# main.net
KiCad netlist of a schematic drawn in Altium Designer
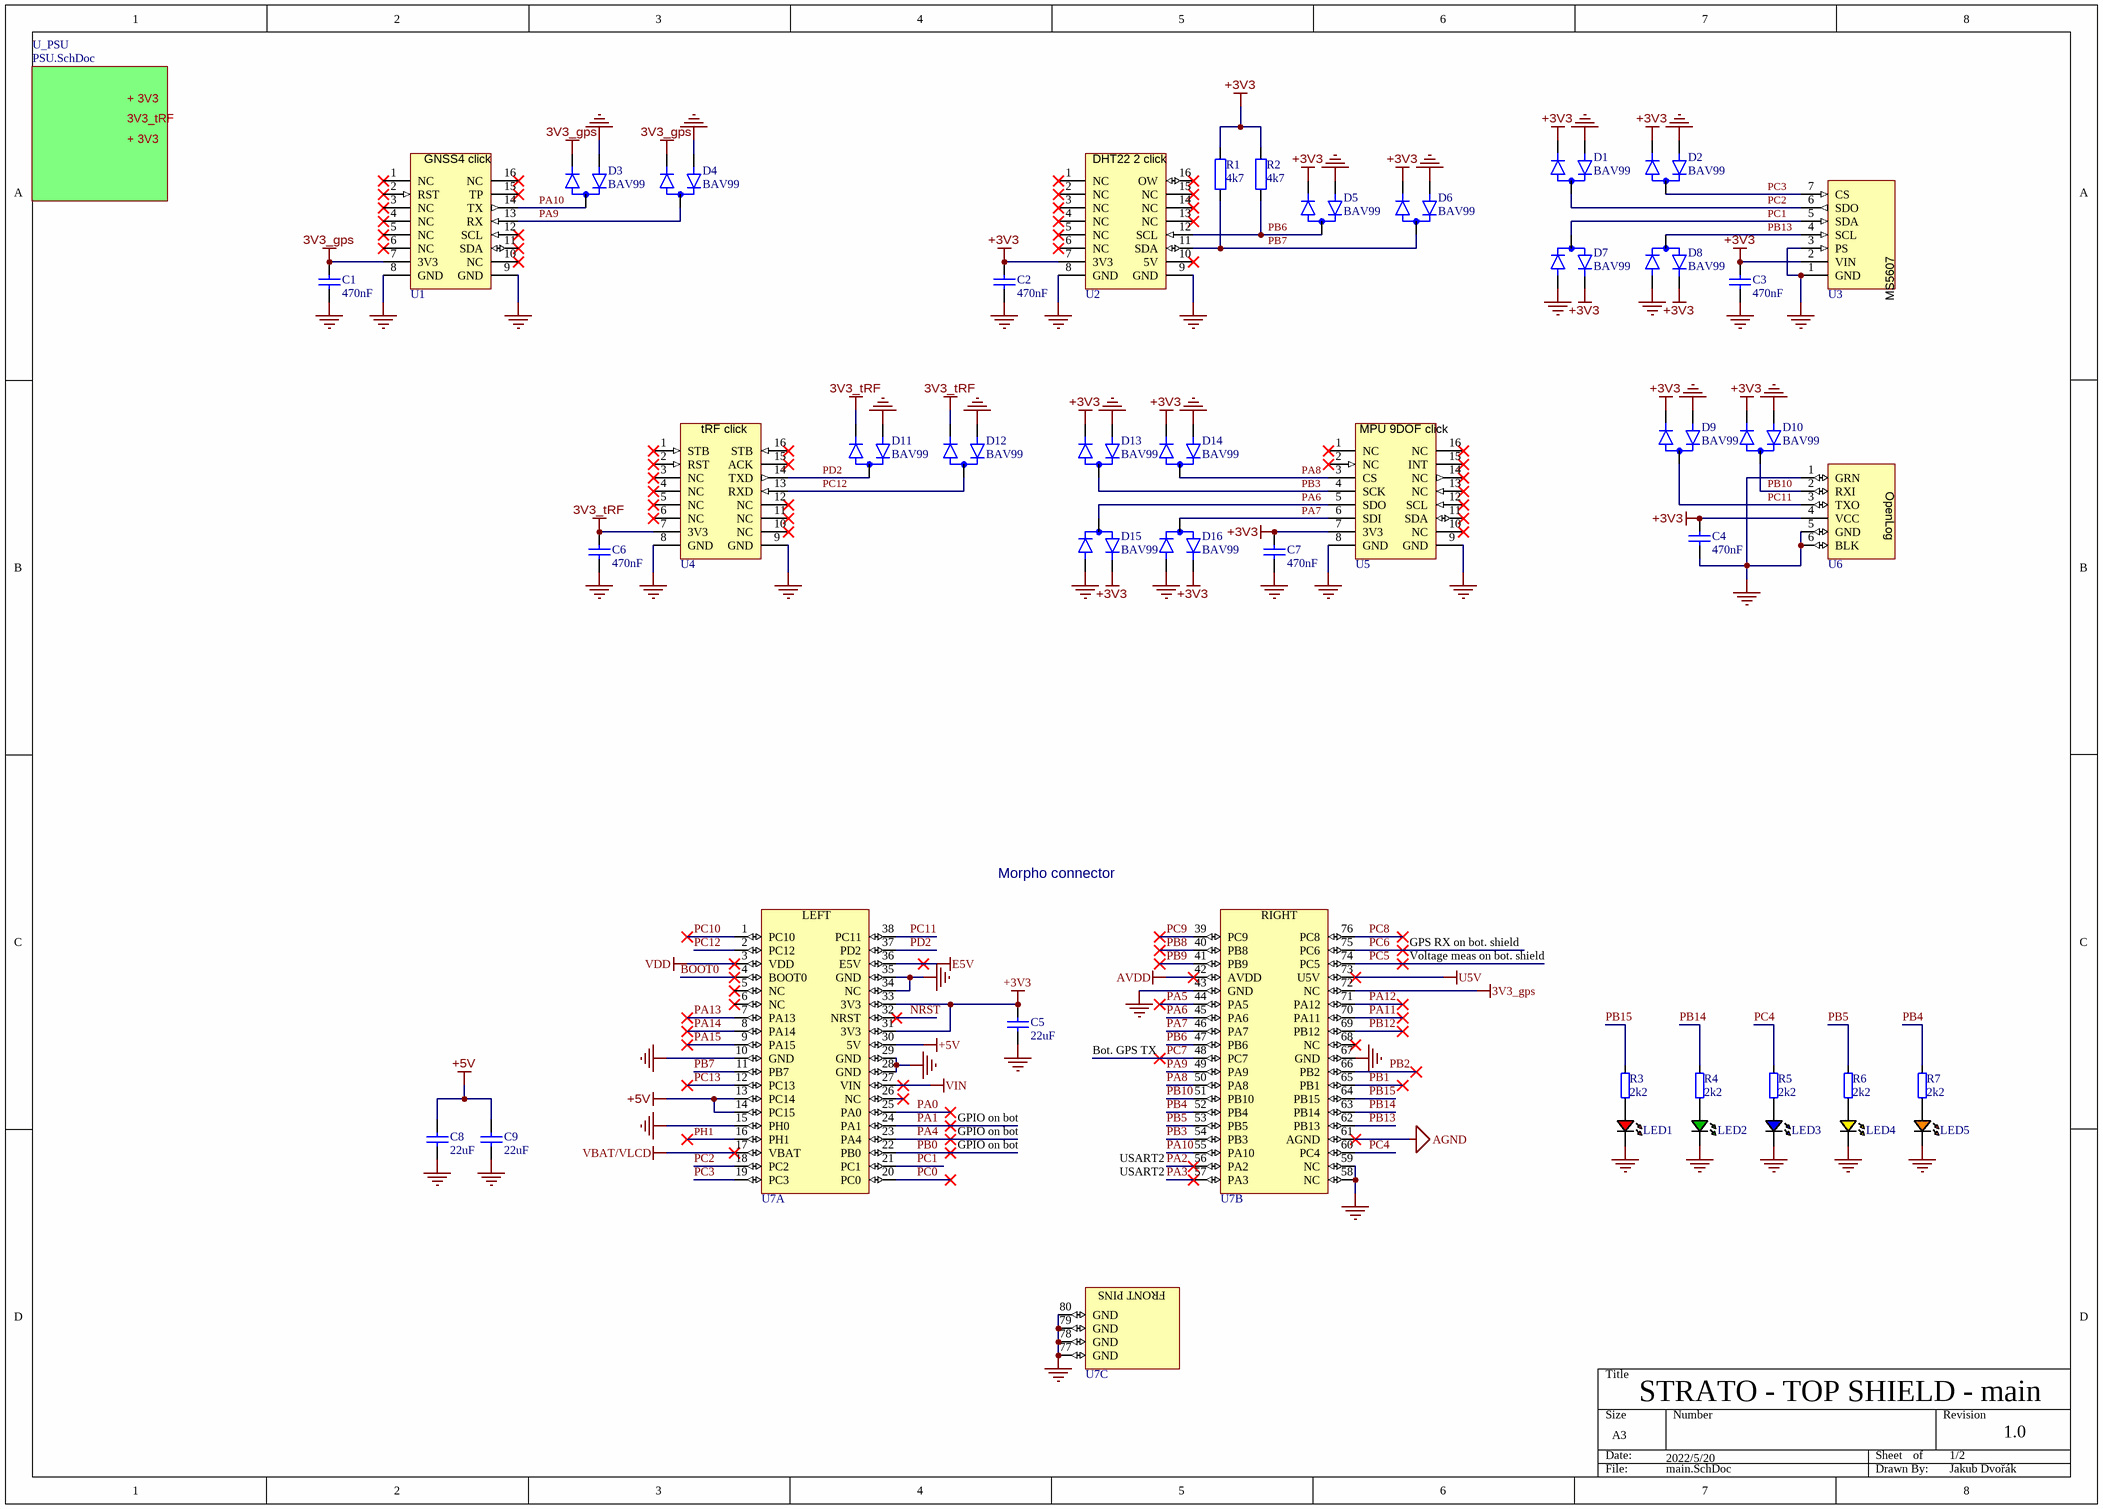
[diagram p0: main.SchDoc]

(export (version "E")
  (design (tool "Eeschema 10.0.6"))
  (components
    (comp (ref "C1")
      (value "470nF")
      (footprint "WCAP-CSGP_0805_L2W1.25H1.25")
      (description "WCAP-CSGP Multilayer Ceramic Chip Capacitor, General Purpose, size 0805, X7R, 470nF, 50V")
      (fields
        (field (name "MANUFACTURER") "Wurth Elektronik")
        (field (name "MANUFACTURER PART NUMBER") "885012207102")
      )
      (libsource (lib "Altium_WCAP-CSGP (rev22a)") (part "885012207102"))
    )
    (comp (ref "C2")
      (value "470nF")
      (footprint "WCAP-CSGP_0805_L2W1.25H1.25")
      (description "WCAP-CSGP Multilayer Ceramic Chip Capacitor, General Purpose, size 0805, X7R, 470nF, 50V")
      (fields
        (field (name "MANUFACTURER") "Wurth Elektronik")
        (field (name "MANUFACTURER PART NUMBER") "885012207102")
      )
      (libsource (lib "Altium_WCAP-CSGP (rev22a)") (part "885012207102"))
    )
    (comp (ref "C3")
      (value "470nF")
      (footprint "WCAP-CSGP_0805_L2W1.25H1.25")
      (description "WCAP-CSGP Multilayer Ceramic Chip Capacitor, General Purpose, size 0805, X7R, 470nF, 50V")
      (fields
        (field (name "MANUFACTURER") "Wurth Elektronik")
        (field (name "MANUFACTURER PART NUMBER") "885012207102")
      )
      (libsource (lib "Altium_WCAP-CSGP (rev22a)") (part "885012207102"))
    )
    (comp (ref "C4")
      (value "470nF")
      (footprint "WCAP-CSGP_0805_L2W1.25H1.25")
      (description "WCAP-CSGP Multilayer Ceramic Chip Capacitor, General Purpose, size 0805, X7R, 470nF, 50V")
      (fields
        (field (name "MANUFACTURER") "Wurth Elektronik")
        (field (name "MANUFACTURER PART NUMBER") "885012207102")
      )
      (libsource (lib "Altium_WCAP-CSGP (rev22a)") (part "885012207102"))
    )
    (comp (ref "C5")
      (value "22uF")
      (footprint "WCAP-CSGP_0805_L2W1.25H1.25")
      (description "WCAP-CSGP Multilayer Ceramic Chip Capacitor, General Purpose, size 0805, X5R, 22uF, 10V")
      (fields
        (field (name "MANUFACTURER") "Wurth Elektronik")
        (field (name "MANUFACTURER PART NUMBER") "885012107011")
      )
      (libsource (lib "Altium_WCAP-CSGP (rev22a)") (part "885012107011"))
    )
    (comp (ref "C6")
      (value "470nF")
      (footprint "WCAP-CSGP_0805_L2W1.25H1.25")
      (description "WCAP-CSGP Multilayer Ceramic Chip Capacitor, General Purpose, size 0805, X7R, 470nF, 50V")
      (fields
        (field (name "MANUFACTURER") "Wurth Elektronik")
        (field (name "MANUFACTURER PART NUMBER") "885012207102")
      )
      (libsource (lib "Altium_WCAP-CSGP (rev22a)") (part "885012207102"))
    )
    (comp (ref "C7")
      (value "470nF")
      (footprint "WCAP-CSGP_0805_L2W1.25H1.25")
      (description "WCAP-CSGP Multilayer Ceramic Chip Capacitor, General Purpose, size 0805, X7R, 470nF, 50V")
      (fields
        (field (name "MANUFACTURER") "Wurth Elektronik")
        (field (name "MANUFACTURER PART NUMBER") "885012207102")
      )
      (libsource (lib "Altium_WCAP-CSGP (rev22a)") (part "885012207102"))
    )
    (comp (ref "C8")
      (value "22uF")
      (footprint "WCAP-CSGP_0805_L2W1.25H1.25")
      (description "WCAP-CSGP Multilayer Ceramic Chip Capacitor, General Purpose, size 0805, X5R, 22uF, 10V")
      (fields
        (field (name "MANUFACTURER") "Wurth Elektronik")
        (field (name "MANUFACTURER PART NUMBER") "885012107011")
      )
      (libsource (lib "Altium_WCAP-CSGP (rev22a)") (part "885012107011"))
    )
    (comp (ref "C9")
      (value "22uF")
      (footprint "WCAP-CSGP_0805_L2W1.25H1.25")
      (description "WCAP-CSGP Multilayer Ceramic Chip Capacitor, General Purpose, size 0805, X5R, 22uF, 10V")
      (fields
        (field (name "MANUFACTURER") "Wurth Elektronik")
        (field (name "MANUFACTURER PART NUMBER") "885012107011")
      )
      (libsource (lib "Altium_WCAP-CSGP (rev22a)") (part "885012107011"))
    )
    (comp (ref "D1")
      (value "BAV99")
      (footprint "SOT95P230X110-3N(SOT23)")
      (libsource (lib "Kubikova integrovana knihovna ") (part "BAV99"))
    )
    (comp (ref "D2")
      (value "BAV99")
      (footprint "SOT95P230X110-3N(SOT23)")
      (libsource (lib "Kubikova integrovana knihovna ") (part "BAV99"))
    )
    (comp (ref "D3")
      (value "BAV99")
      (footprint "SOT95P230X110-3N(SOT23)")
      (libsource (lib "Kubikova integrovana knihovna ") (part "BAV99"))
    )
    (comp (ref "D4")
      (value "BAV99")
      (footprint "SOT95P230X110-3N(SOT23)")
      (libsource (lib "Kubikova integrovana knihovna ") (part "BAV99"))
    )
    (comp (ref "D5")
      (value "BAV99")
      (footprint "SOT95P230X110-3N(SOT23)")
      (libsource (lib "Kubikova integrovana knihovna ") (part "BAV99"))
    )
    (comp (ref "D6")
      (value "BAV99")
      (footprint "SOT95P230X110-3N(SOT23)")
      (libsource (lib "Kubikova integrovana knihovna ") (part "BAV99"))
    )
    (comp (ref "D7")
      (value "BAV99")
      (footprint "SOT95P230X110-3N(SOT23)")
      (libsource (lib "Kubikova integrovana knihovna ") (part "BAV99"))
    )
    (comp (ref "D8")
      (value "BAV99")
      (footprint "SOT95P230X110-3N(SOT23)")
      (libsource (lib "Kubikova integrovana knihovna ") (part "BAV99"))
    )
    (comp (ref "D9")
      (value "BAV99")
      (footprint "SOT95P230X110-3N(SOT23)")
      (libsource (lib "Kubikova integrovana knihovna ") (part "BAV99"))
    )
    (comp (ref "D10")
      (value "BAV99")
      (footprint "SOT95P230X110-3N(SOT23)")
      (libsource (lib "Kubikova integrovana knihovna ") (part "BAV99"))
    )
    (comp (ref "D11")
      (value "BAV99")
      (footprint "SOT95P230X110-3N(SOT23)")
      (libsource (lib "Kubikova integrovana knihovna ") (part "BAV99"))
    )
    (comp (ref "D12")
      (value "BAV99")
      (footprint "SOT95P230X110-3N(SOT23)")
      (libsource (lib "Kubikova integrovana knihovna ") (part "BAV99"))
    )
    (comp (ref "D13")
      (value "BAV99")
      (footprint "SOT95P230X110-3N(SOT23)")
      (libsource (lib "Kubikova integrovana knihovna ") (part "BAV99"))
    )
    (comp (ref "D14")
      (value "BAV99")
      (footprint "SOT95P230X110-3N(SOT23)")
      (libsource (lib "Kubikova integrovana knihovna ") (part "BAV99"))
    )
    (comp (ref "D15")
      (value "BAV99")
      (footprint "SOT95P230X110-3N(SOT23)")
      (libsource (lib "Kubikova integrovana knihovna ") (part "BAV99"))
    )
    (comp (ref "D16")
      (value "BAV99")
      (footprint "SOT95P230X110-3N(SOT23)")
      (libsource (lib "Kubikova integrovana knihovna ") (part "BAV99"))
    )
    (comp (ref "LED1")
      (value "red")
      (footprint "0805LEDR")
      (libsource (lib "all_in_one_library") (part "LEDR_0805"))
    )
    (comp (ref "LED2")
      (value "green")
      (footprint "0805LEDG")
      (libsource (lib "all_in_one_library") (part "LEDG_0805"))
    )
    (comp (ref "LED3")
      (value "blue")
      (footprint "0805LEDB")
      (libsource (lib "all_in_one_library") (part "LEDB_0805"))
    )
    (comp (ref "LED4")
      (value "yellow")
      (footprint "0805LEDYell")
      (libsource (lib "all_in_one_library") (part "LEDYell_0805"))
    )
    (comp (ref "LED5")
      (value "orange")
      (footprint "0805LEDOra")
      (libsource (lib "all_in_one_library") (part "LEDOra_0805"))
    )
    (comp (ref "R1")
      (value "4k7")
      (footprint "RES_0603")
      (description "4700.00")
      (fields (field (name "Comment") "Thick film"))
      (libsource (lib "all_in_one_library") (part "RES_4k7_5%_0603"))
    )
    (comp (ref "R2")
      (value "4k7")
      (footprint "RES_0603")
      (description "4700.00")
      (fields (field (name "Comment") "Thick film"))
      (libsource (lib "all_in_one_library") (part "RES_4k7_5%_0603"))
    )
    (comp (ref "R3")
      (value "2k2")
      (footprint "RES_0603")
      (description "2200.00")
      (fields (field (name "Comment") "Thick film"))
      (libsource (lib "all_in_one_library") (part "RES_2k2_5%_0603"))
    )
    (comp (ref "R4")
      (value "2k2")
      (footprint "RES_0603")
      (description "2200.00")
      (fields (field (name "Comment") "Thick film"))
      (libsource (lib "all_in_one_library") (part "RES_2k2_5%_0603"))
    )
    (comp (ref "R5")
      (value "2k2")
      (footprint "RES_0603")
      (description "2200.00")
      (fields (field (name "Comment") "Thick film"))
      (libsource (lib "all_in_one_library") (part "RES_2k2_5%_0603"))
    )
    (comp (ref "R6")
      (value "2k2")
      (footprint "RES_0603")
      (description "2200.00")
      (fields (field (name "Comment") "Thick film"))
      (libsource (lib "all_in_one_library") (part "RES_2k2_5%_0603"))
    )
    (comp (ref "R7")
      (value "2k2")
      (footprint "RES_0603")
      (description "2200.00")
      (fields (field (name "Comment") "Thick film"))
      (libsource (lib "all_in_one_library") (part "RES_2k2_5%_0603"))
    )
    (comp (ref "U1")
      (value "GNSS4 cllick")
      (footprint "GNSS4 click")
      (libsource (lib "Nucleo f466") (part "GNSS4 cllick"))
    )
    (comp (ref "U2")
      (value "DHT22 2 click")
      (footprint "DHT22 2 click")
      (libsource (lib "Nucleo f466") (part "DHT22 2 click"))
    )
    (comp (ref "U3") (value "MS5607") (footprint "MS5607") (libsource (lib "Nucleo f466") (part "MS5607")))
    (comp (ref "U4")
      (value "tRF click")
      (footprint "tRF click")
      (libsource (lib "Nucleo f466") (part "tRF click"))
    )
    (comp (ref "U5")
      (value "MPU 9DOF click")
      (footprint "MPU 9DOF click")
      (libsource (lib "Nucleo f466") (part "MPU 9DOF click"))
    )
    (comp (ref "U6") (value "OpenLog") (footprint "OpenLog") (libsource (lib "Nucleo f466") (part "OpenLog")))
    (comp (ref "U7")
      (value "NUCLEO F466 MORPHO LEFT")
      (footprint "Nucleo_bot_pads")
      (libsource (lib "Kubikova ultra knihovna") (part "NUCLEO F466 MORPHO LEFT"))
    )
  )
  (nets
    (net (code "1") (name "+3V3") (class "Default")
      (node (ref "C2") (pin "2") (pinfunction "2_2") (pintype "passive"))
      (node (ref "C3") (pin "2") (pinfunction "2_2") (pintype "passive"))
      (node (ref "C4") (pin "2") (pinfunction "2_2") (pintype "passive"))
      (node (ref "C5") (pin "2") (pinfunction "2_2") (pintype "passive"))
      (node (ref "C7") (pin "2") (pinfunction "2_2") (pintype "passive"))
      (node (ref "D1") (pin "2") (pinfunction "C2_2") (pintype "passive"))
      (node (ref "D10") (pin "2") (pinfunction "C2_2") (pintype "passive"))
      (node (ref "D13") (pin "2") (pinfunction "C2_2") (pintype "passive"))
      (node (ref "D14") (pin "2") (pinfunction "C2_2") (pintype "passive"))
      (node (ref "D15") (pin "2") (pinfunction "C2_2") (pintype "passive"))
      (node (ref "D16") (pin "2") (pinfunction "C2_2") (pintype "passive"))
      (node (ref "D2") (pin "2") (pinfunction "C2_2") (pintype "passive"))
      (node (ref "D5") (pin "2") (pinfunction "C2_2") (pintype "passive"))
      (node (ref "D6") (pin "2") (pinfunction "C2_2") (pintype "passive"))
      (node (ref "D7") (pin "2") (pinfunction "C2_2") (pintype "passive"))
      (node (ref "D8") (pin "2") (pinfunction "C2_2") (pintype "passive"))
      (node (ref "D9") (pin "2") (pinfunction "C2_2") (pintype "passive"))
      (node (ref "R1") (pin "2") (pinfunction "2_2") (pintype "passive"))
      (node (ref "R2") (pin "2") (pinfunction "2_2") (pintype "passive"))
      (node (ref "U2") (pin "7") (pinfunction "3V3_7") (pintype "power_in"))
      (node (ref "U3") (pin "2") (pinfunction "VIN_2") (pintype "power_in"))
      (node (ref "U5") (pin "7") (pinfunction "3V3_7") (pintype "power_in"))
      (node (ref "U6") (pin "4") (pinfunction "VCC_4") (pintype "power_in"))
      (node (ref "U7") (pin "31") (pinfunction "3V3_31") (pintype "bidirectional"))
      (node (ref "U7") (pin "33") (pinfunction "3V3_33") (pintype "bidirectional"))
    )
    (net (code "2") (name "+5V") (class "Default")
      (node (ref "C8") (pin "2") (pinfunction "2_2") (pintype "passive"))
      (node (ref "C9") (pin "2") (pinfunction "2_2") (pintype "passive"))
      (node (ref "U7") (pin "13") (pinfunction "PC14_13") (pintype "bidirectional"))
      (node (ref "U7") (pin "14") (pinfunction "PC15_14") (pintype "bidirectional"))
      (node (ref "U7") (pin "30") (pinfunction "5V_30") (pintype "bidirectional"))
    )
    (net (code "3") (name "/BOOT0") (class "Default")
      (node (ref "U7") (pin "4") (pinfunction "BOOT0_4") (pintype "bidirectional+no_connect"))
    )
    (net (code "4") (name "/NRST") (class "Default")
      (node (ref "U7") (pin "32") (pinfunction "NRST_32") (pintype "bidirectional+no_connect"))
    )
    (net (code "5") (name "/PA0") (class "Default")
      (node (ref "U7") (pin "25") (pinfunction "PA0_25") (pintype "bidirectional+no_connect"))
    )
    (net (code "6") (name "/PA1") (class "Default")
      (node (ref "U7") (pin "24") (pinfunction "PA1_24") (pintype "bidirectional"))
    )
    (net (code "7") (name "/PA2") (class "Default")
      (node (ref "U7") (pin "56") (pinfunction "PA2_56") (pintype "bidirectional+no_connect"))
    )
    (net (code "8") (name "/PA3") (class "Default")
      (node (ref "U7") (pin "57") (pinfunction "PA3_57") (pintype "bidirectional+no_connect"))
    )
    (net (code "9") (name "/PA4") (class "Default")
      (node (ref "U7") (pin "23") (pinfunction "PA4_23") (pintype "bidirectional"))
    )
    (net (code "10") (name "/PA5") (class "Default")
      (node (ref "U7") (pin "44") (pinfunction "PA5_44") (pintype "bidirectional+no_connect"))
    )
    (net (code "11") (name "/PA6") (class "Default")
      (node (ref "D15") (pin "3") (pinfunction "C1A2_3") (pintype "passive"))
      (node (ref "U5") (pin "5") (pinfunction "SDO_5") (pintype "tri_state"))
      (node (ref "U7") (pin "45") (pinfunction "PA6_45") (pintype "bidirectional"))
    )
    (net (code "12") (name "/PA7") (class "Default")
      (node (ref "D16") (pin "3") (pinfunction "C1A2_3") (pintype "passive"))
      (node (ref "U5") (pin "6") (pinfunction "SDI_6") (pintype "tri_state"))
      (node (ref "U7") (pin "46") (pinfunction "PA7_46") (pintype "bidirectional"))
    )
    (net (code "13") (name "/PA8") (class "Default")
      (node (ref "D14") (pin "3") (pinfunction "C1A2_3") (pintype "passive"))
      (node (ref "U5") (pin "3") (pinfunction "CS_3") (pintype "tri_state"))
      (node (ref "U7") (pin "50") (pinfunction "PA8_50") (pintype "bidirectional"))
    )
    (net (code "14") (name "/PA9") (class "Default")
      (node (ref "D4") (pin "3") (pinfunction "C1A2_3") (pintype "passive"))
      (node (ref "U1") (pin "13") (pinfunction "RX_13") (pintype "input"))
      (node (ref "U7") (pin "49") (pinfunction "PA9_49") (pintype "bidirectional"))
    )
    (net (code "15") (name "/PA10") (class "Default")
      (node (ref "D3") (pin "3") (pinfunction "C1A2_3") (pintype "passive"))
      (node (ref "U1") (pin "14") (pinfunction "TX_14") (pintype "output"))
      (node (ref "U7") (pin "55") (pinfunction "PA10_55") (pintype "bidirectional"))
    )
    (net (code "16") (name "/PA11") (class "Default")
      (node (ref "U7") (pin "70") (pinfunction "PA11_70") (pintype "bidirectional+no_connect"))
    )
    (net (code "17") (name "/PA12") (class "Default")
      (node (ref "U7") (pin "71") (pinfunction "PA12_71") (pintype "bidirectional+no_connect"))
    )
    (net (code "18") (name "/PA13") (class "Default")
      (node (ref "U7") (pin "7") (pinfunction "PA13_7") (pintype "bidirectional+no_connect"))
    )
    (net (code "19") (name "/PA14") (class "Default")
      (node (ref "U7") (pin "8") (pinfunction "PA14_8") (pintype "bidirectional+no_connect"))
    )
    (net (code "20") (name "/PA15") (class "Default")
      (node (ref "U7") (pin "9") (pinfunction "PA15_9") (pintype "bidirectional+no_connect"))
    )
    (net (code "21") (name "/PB0") (class "Default")
      (node (ref "U7") (pin "22") (pinfunction "PB0_22") (pintype "bidirectional"))
    )
    (net (code "22") (name "/PB1") (class "Default")
      (node (ref "U7") (pin "65") (pinfunction "PB1_65") (pintype "bidirectional+no_connect"))
    )
    (net (code "23") (name "/PB2") (class "Default")
      (node (ref "U7") (pin "66") (pinfunction "PB2_66") (pintype "bidirectional+no_connect"))
    )
    (net (code "24") (name "/PB3") (class "Default")
      (node (ref "D13") (pin "3") (pinfunction "C1A2_3") (pintype "passive"))
      (node (ref "U5") (pin "4") (pinfunction "SCK_4") (pintype "tri_state"))
      (node (ref "U7") (pin "54") (pinfunction "PB3_54") (pintype "bidirectional"))
    )
    (net (code "25") (name "/PB4") (class "Default")
      (node (ref "R7") (pin "2") (pinfunction "2_2") (pintype "passive"))
      (node (ref "U7") (pin "52") (pinfunction "PB4_52") (pintype "bidirectional"))
    )
    (net (code "26") (name "/PB5") (class "Default")
      (node (ref "R6") (pin "2") (pinfunction "2_2") (pintype "passive"))
      (node (ref "U7") (pin "53") (pinfunction "PB5_53") (pintype "bidirectional"))
    )
    (net (code "27") (name "/PB6") (class "Default")
      (node (ref "D5") (pin "3") (pinfunction "C1A2_3") (pintype "passive"))
      (node (ref "R2") (pin "1") (pinfunction "1_1") (pintype "passive"))
      (node (ref "U2") (pin "12") (pinfunction "SCL_12") (pintype "input"))
      (node (ref "U7") (pin "47") (pinfunction "PB6_47") (pintype "bidirectional"))
    )
    (net (code "28") (name "/PB7") (class "Default")
      (node (ref "D6") (pin "3") (pinfunction "C1A2_3") (pintype "passive"))
      (node (ref "R1") (pin "1") (pinfunction "1_1") (pintype "passive"))
      (node (ref "U2") (pin "11") (pinfunction "SDA_11") (pintype "bidirectional"))
      (node (ref "U7") (pin "11") (pinfunction "PB7_11") (pintype "bidirectional"))
    )
    (net (code "29") (name "/PB8") (class "Default")
      (node (ref "U7") (pin "40") (pinfunction "PB8_40") (pintype "bidirectional+no_connect"))
    )
    (net (code "30") (name "/PB9") (class "Default")
      (node (ref "U7") (pin "41") (pinfunction "PB9_41") (pintype "bidirectional+no_connect"))
    )
    (net (code "31") (name "/PB10") (class "Default")
      (node (ref "D10") (pin "3") (pinfunction "C1A2_3") (pintype "passive"))
      (node (ref "U6") (pin "2") (pinfunction "RXI_2") (pintype "bidirectional"))
      (node (ref "U7") (pin "51") (pinfunction "PB10_51") (pintype "bidirectional"))
    )
    (net (code "32") (name "/PB12") (class "Default")
      (node (ref "U7") (pin "69") (pinfunction "PB12_69") (pintype "bidirectional+no_connect"))
    )
    (net (code "33") (name "/PB13") (class "Default")
      (node (ref "D8") (pin "3") (pinfunction "C1A2_3") (pintype "passive"))
      (node (ref "U3") (pin "4") (pinfunction "SCL_4") (pintype "input"))
      (node (ref "U7") (pin "62") (pinfunction "PB13_62") (pintype "bidirectional"))
    )
    (net (code "34") (name "/PB14") (class "Default")
      (node (ref "R4") (pin "2") (pinfunction "2_2") (pintype "passive"))
      (node (ref "U7") (pin "63") (pinfunction "PB14_63") (pintype "bidirectional"))
    )
    (net (code "35") (name "/PB15") (class "Default")
      (node (ref "R3") (pin "2") (pinfunction "2_2") (pintype "passive"))
      (node (ref "U7") (pin "64") (pinfunction "PB15_64") (pintype "bidirectional"))
    )
    (net (code "36") (name "/PC0") (class "Default")
      (node (ref "U7") (pin "20") (pinfunction "PC0_20") (pintype "bidirectional+no_connect"))
    )
    (net (code "37") (name "/PC1") (class "Default")
      (node (ref "D7") (pin "3") (pinfunction "C1A2_3") (pintype "passive"))
      (node (ref "U3") (pin "5") (pinfunction "SDA_5") (pintype "input"))
      (node (ref "U7") (pin "21") (pinfunction "PC1_21") (pintype "bidirectional"))
    )
    (net (code "38") (name "/PC2") (class "Default")
      (node (ref "D1") (pin "3") (pinfunction "C1A2_3") (pintype "passive"))
      (node (ref "U3") (pin "6") (pinfunction "SDO_6") (pintype "output"))
      (node (ref "U7") (pin "18") (pinfunction "PC2_18") (pintype "bidirectional"))
    )
    (net (code "39") (name "/PC3") (class "Default")
      (node (ref "D2") (pin "3") (pinfunction "C1A2_3") (pintype "passive"))
      (node (ref "U3") (pin "7") (pinfunction "CS_7") (pintype "input"))
      (node (ref "U7") (pin "19") (pinfunction "PC3_19") (pintype "bidirectional"))
    )
    (net (code "40") (name "/PC4") (class "Default")
      (node (ref "R5") (pin "2") (pinfunction "2_2") (pintype "passive"))
      (node (ref "U7") (pin "60") (pinfunction "PC4_60") (pintype "bidirectional"))
    )
    (net (code "41") (name "/PC5") (class "Default")
      (node (ref "U7") (pin "74") (pinfunction "PC5_74") (pintype "bidirectional"))
    )
    (net (code "42") (name "/PC6") (class "Default")
      (node (ref "U7") (pin "75") (pinfunction "PC6_75") (pintype "bidirectional"))
    )
    (net (code "43") (name "/PC7") (class "Default")
      (node (ref "U7") (pin "48") (pinfunction "PC7_48") (pintype "bidirectional"))
    )
    (net (code "44") (name "/PC8") (class "Default")
      (node (ref "U7") (pin "76") (pinfunction "PC8_76") (pintype "bidirectional+no_connect"))
    )
    (net (code "45") (name "/PC9") (class "Default")
      (node (ref "U7") (pin "39") (pinfunction "PC9_39") (pintype "bidirectional+no_connect"))
    )
    (net (code "46") (name "/PC10") (class "Default")
      (node (ref "U7") (pin "1") (pinfunction "PC10_1") (pintype "bidirectional+no_connect"))
    )
    (net (code "47") (name "/PC11") (class "Default")
      (node (ref "D9") (pin "3") (pinfunction "C1A2_3") (pintype "passive"))
      (node (ref "U6") (pin "3") (pinfunction "TXO_3") (pintype "bidirectional"))
      (node (ref "U7") (pin "38") (pinfunction "PC11_38") (pintype "bidirectional"))
    )
    (net (code "48") (name "/PC12") (class "Default")
      (node (ref "D12") (pin "3") (pinfunction "C1A2_3") (pintype "passive"))
      (node (ref "U4") (pin "13") (pinfunction "RXD_13") (pintype "input"))
      (node (ref "U7") (pin "2") (pinfunction "PC12_2") (pintype "bidirectional"))
    )
    (net (code "49") (name "/PC13") (class "Default")
      (node (ref "U7") (pin "12") (pinfunction "PC13_12") (pintype "bidirectional+no_connect"))
    )
    (net (code "50") (name "/PD2") (class "Default")
      (node (ref "D11") (pin "3") (pinfunction "C1A2_3") (pintype "passive"))
      (node (ref "U4") (pin "14") (pinfunction "TXD_14") (pintype "output"))
      (node (ref "U7") (pin "37") (pinfunction "PD2_37") (pintype "bidirectional"))
    )
    (net (code "51") (name "/PH1") (class "Default")
      (node (ref "U7") (pin "16") (pinfunction "PH1_16") (pintype "bidirectional+no_connect"))
    )
    (net (code "52") (name "3V3_gps") (class "Default")
      (node (ref "C1") (pin "2") (pinfunction "2_2") (pintype "passive"))
      (node (ref "D3") (pin "2") (pinfunction "C2_2") (pintype "passive"))
      (node (ref "D4") (pin "2") (pinfunction "C2_2") (pintype "passive"))
      (node (ref "U1") (pin "7") (pinfunction "3V3_7") (pintype "power_in"))
      (node (ref "U7") (pin "72") (pinfunction "NC_72") (pintype "bidirectional"))
    )
    (net (code "53") (name "3V3_tRF") (class "Default")
      (node (ref "C6") (pin "2") (pinfunction "2_2") (pintype "passive"))
      (node (ref "D11") (pin "2") (pinfunction "C2_2") (pintype "passive"))
      (node (ref "D12") (pin "2") (pinfunction "C2_2") (pintype "passive"))
      (node (ref "U4") (pin "7") (pinfunction "3V3_7") (pintype "power_in"))
    )
    (net (code "54") (name "AGND") (class "Default")
      (node (ref "U7") (pin "61") (pinfunction "AGND_61") (pintype "bidirectional"))
    )
    (net (code "55") (name "AVDD") (class "Default")
      (node (ref "U7") (pin "42") (pinfunction "AVDD_42") (pintype "bidirectional"))
    )
    (net (code "56") (name "E5V") (class "Default")
      (node (ref "U7") (pin "36") (pinfunction "E5V_36") (pintype "bidirectional"))
    )
    (net (code "57") (name "GND") (class "Default")
      (node (ref "C1") (pin "1") (pinfunction "1_1") (pintype "passive"))
      (node (ref "C2") (pin "1") (pinfunction "1_1") (pintype "passive"))
      (node (ref "C3") (pin "1") (pinfunction "1_1") (pintype "passive"))
      (node (ref "C4") (pin "1") (pinfunction "1_1") (pintype "passive"))
      (node (ref "C5") (pin "1") (pinfunction "1_1") (pintype "passive"))
      (node (ref "C6") (pin "1") (pinfunction "1_1") (pintype "passive"))
      (node (ref "C7") (pin "1") (pinfunction "1_1") (pintype "passive"))
      (node (ref "C8") (pin "1") (pinfunction "1_1") (pintype "passive"))
      (node (ref "C9") (pin "1") (pinfunction "1_1") (pintype "passive"))
      (node (ref "D1") (pin "1") (pinfunction "A1_1") (pintype "passive"))
      (node (ref "D10") (pin "1") (pinfunction "A1_1") (pintype "passive"))
      (node (ref "D11") (pin "1") (pinfunction "A1_1") (pintype "passive"))
      (node (ref "D12") (pin "1") (pinfunction "A1_1") (pintype "passive"))
      (node (ref "D13") (pin "1") (pinfunction "A1_1") (pintype "passive"))
      (node (ref "D14") (pin "1") (pinfunction "A1_1") (pintype "passive"))
      (node (ref "D15") (pin "1") (pinfunction "A1_1") (pintype "passive"))
      (node (ref "D16") (pin "1") (pinfunction "A1_1") (pintype "passive"))
      (node (ref "D2") (pin "1") (pinfunction "A1_1") (pintype "passive"))
      (node (ref "D3") (pin "1") (pinfunction "A1_1") (pintype "passive"))
      (node (ref "D4") (pin "1") (pinfunction "A1_1") (pintype "passive"))
      (node (ref "D5") (pin "1") (pinfunction "A1_1") (pintype "passive"))
      (node (ref "D6") (pin "1") (pinfunction "A1_1") (pintype "passive"))
      (node (ref "D7") (pin "1") (pinfunction "A1_1") (pintype "passive"))
      (node (ref "D8") (pin "1") (pinfunction "A1_1") (pintype "passive"))
      (node (ref "D9") (pin "1") (pinfunction "A1_1") (pintype "passive"))
      (node (ref "LED1") (pin "K") (pinfunction "K_K") (pintype "passive"))
      (node (ref "LED2") (pin "K") (pinfunction "K_K") (pintype "passive"))
      (node (ref "LED3") (pin "K") (pinfunction "K_K") (pintype "passive"))
      (node (ref "LED4") (pin "K") (pinfunction "K_K") (pintype "passive"))
      (node (ref "LED5") (pin "K") (pinfunction "K_K") (pintype "passive"))
      (node (ref "U1") (pin "8") (pinfunction "GND_8") (pintype "power_in"))
      (node (ref "U1") (pin "9") (pinfunction "GND_9") (pintype "power_in"))
      (node (ref "U2") (pin "8") (pinfunction "GND_8") (pintype "power_in"))
      (node (ref "U2") (pin "9") (pinfunction "GND_9") (pintype "power_in"))
      (node (ref "U3") (pin "1") (pinfunction "GND_1") (pintype "power_in"))
      (node (ref "U3") (pin "3") (pinfunction "PS_3") (pintype "input"))
      (node (ref "U4") (pin "8") (pinfunction "GND_8") (pintype "power_in"))
      (node (ref "U4") (pin "9") (pinfunction "GND_9") (pintype "power_in"))
      (node (ref "U5") (pin "8") (pinfunction "GND_8") (pintype "power_in"))
      (node (ref "U5") (pin "9") (pinfunction "GND_9") (pintype "power_in"))
      (node (ref "U6") (pin "1") (pinfunction "GRN_1") (pintype "bidirectional"))
      (node (ref "U6") (pin "5") (pinfunction "GND_5") (pintype "bidirectional"))
      (node (ref "U6") (pin "6") (pinfunction "BLK_6") (pintype "bidirectional"))
      (node (ref "U7") (pin "10") (pinfunction "GND_10") (pintype "bidirectional"))
      (node (ref "U7") (pin "15") (pinfunction "PH0_15") (pintype "bidirectional"))
      (node (ref "U7") (pin "28") (pinfunction "GND_28") (pintype "bidirectional"))
      (node (ref "U7") (pin "29") (pinfunction "GND_29") (pintype "bidirectional"))
      (node (ref "U7") (pin "34") (pinfunction "NC_34") (pintype "bidirectional"))
      (node (ref "U7") (pin "35") (pinfunction "GND_35") (pintype "bidirectional"))
      (node (ref "U7") (pin "43") (pinfunction "GND_43") (pintype "bidirectional"))
      (node (ref "U7") (pin "58") (pinfunction "NC_58") (pintype "bidirectional"))
      (node (ref "U7") (pin "59") (pinfunction "NC_59") (pintype "bidirectional"))
      (node (ref "U7") (pin "67") (pinfunction "GND_67") (pintype "bidirectional"))
      (node (ref "U7") (pin "77") (pinfunction "GND_77") (pintype "bidirectional"))
      (node (ref "U7") (pin "78") (pinfunction "GND_78") (pintype "bidirectional"))
      (node (ref "U7") (pin "79") (pinfunction "GND_79") (pintype "bidirectional"))
      (node (ref "U7") (pin "80") (pinfunction "GND_80") (pintype "bidirectional"))
    )
    (net (code "58") (name "Net-(LED1-PadA)") (class "Default")
      (node (ref "LED1") (pin "A") (pinfunction "A_A") (pintype "passive"))
      (node (ref "R3") (pin "1") (pinfunction "1_1") (pintype "passive"))
    )
    (net (code "59") (name "Net-(LED2-PadA)") (class "Default")
      (node (ref "LED2") (pin "A") (pinfunction "A_A") (pintype "passive"))
      (node (ref "R4") (pin "1") (pinfunction "1_1") (pintype "passive"))
    )
    (net (code "60") (name "Net-(LED3-PadA)") (class "Default")
      (node (ref "LED3") (pin "A") (pinfunction "A_A") (pintype "passive"))
      (node (ref "R5") (pin "1") (pinfunction "1_1") (pintype "passive"))
    )
    (net (code "61") (name "Net-(LED4-PadA)") (class "Default")
      (node (ref "LED4") (pin "A") (pinfunction "A_A") (pintype "passive"))
      (node (ref "R6") (pin "1") (pinfunction "1_1") (pintype "passive"))
    )
    (net (code "62") (name "Net-(LED5-PadA)") (class "Default")
      (node (ref "LED5") (pin "A") (pinfunction "A_A") (pintype "passive"))
      (node (ref "R7") (pin "1") (pinfunction "1_1") (pintype "passive"))
    )
    (net (code "63") (name "U5V") (class "Default")
      (node (ref "U7") (pin "73") (pinfunction "U5V_73") (pintype "bidirectional"))
    )
    (net (code "64") (name "VBAT{slash}VLCD") (class "Default")
      (node (ref "U7") (pin "17") (pinfunction "VBAT_17") (pintype "bidirectional"))
    )
    (net (code "65") (name "VDD") (class "Default")
      (node (ref "U7") (pin "3") (pinfunction "VDD_3") (pintype "bidirectional"))
    )
    (net (code "66") (name "VIN") (class "Default")
      (node (ref "U7") (pin "27") (pinfunction "VIN_27") (pintype "bidirectional"))
    )
    (net (code "67") (name "unconnected-(U1-NC-Pad1)") (class "Default")
      (node (ref "U1") (pin "1") (pinfunction "NC_1") (pintype "tri_state+no_connect"))
    )
    (net (code "68") (name "unconnected-(U1-NC-Pad3)") (class "Default")
      (node (ref "U1") (pin "3") (pinfunction "NC_3") (pintype "tri_state+no_connect"))
    )
    (net (code "69") (name "unconnected-(U1-NC-Pad4)") (class "Default")
      (node (ref "U1") (pin "4") (pinfunction "NC_4") (pintype "tri_state+no_connect"))
    )
    (net (code "70") (name "unconnected-(U1-NC-Pad5)") (class "Default")
      (node (ref "U1") (pin "5") (pinfunction "NC_5") (pintype "tri_state+no_connect"))
    )
    (net (code "71") (name "unconnected-(U1-NC-Pad6)") (class "Default")
      (node (ref "U1") (pin "6") (pinfunction "NC_6") (pintype "tri_state+no_connect"))
    )
    (net (code "72") (name "unconnected-(U1-NC-Pad10)") (class "Default")
      (node (ref "U1") (pin "10") (pinfunction "NC_10") (pintype "open_emitter+no_connect"))
    )
    (net (code "73") (name "unconnected-(U1-NC-Pad16)") (class "Default")
      (node (ref "U1") (pin "16") (pinfunction "NC_16") (pintype "tri_state+no_connect"))
    )
    (net (code "74") (name "unconnected-(U1-RST-Pad2)") (class "Default")
      (node (ref "U1") (pin "2") (pinfunction "RST_2") (pintype "input+no_connect"))
    )
    (net (code "75") (name "unconnected-(U1-SCL-Pad12)") (class "Default")
      (node (ref "U1") (pin "12") (pinfunction "SCL_12") (pintype "input+no_connect"))
    )
    (net (code "76") (name "unconnected-(U1-SDA-Pad11)") (class "Default")
      (node (ref "U1") (pin "11") (pinfunction "SDA_11") (pintype "bidirectional+no_connect"))
    )
    (net (code "77") (name "unconnected-(U1-TP-Pad15)") (class "Default")
      (node (ref "U1") (pin "15") (pinfunction "TP_15") (pintype "tri_state+no_connect"))
    )
    (net (code "78") (name "unconnected-(U2-5V-Pad10)") (class "Default")
      (node (ref "U2") (pin "10") (pinfunction "5V_10") (pintype "power_in+no_connect"))
    )
    (net (code "79") (name "unconnected-(U2-NC-Pad1)") (class "Default")
      (node (ref "U2") (pin "1") (pinfunction "NC_1") (pintype "tri_state+no_connect"))
    )
    (net (code "80") (name "unconnected-(U2-NC-Pad2)") (class "Default")
      (node (ref "U2") (pin "2") (pinfunction "NC_2") (pintype "tri_state+no_connect"))
    )
    (net (code "81") (name "unconnected-(U2-NC-Pad3)") (class "Default")
      (node (ref "U2") (pin "3") (pinfunction "NC_3") (pintype "tri_state+no_connect"))
    )
    (net (code "82") (name "unconnected-(U2-NC-Pad4)") (class "Default")
      (node (ref "U2") (pin "4") (pinfunction "NC_4") (pintype "tri_state+no_connect"))
    )
    (net (code "83") (name "unconnected-(U2-NC-Pad5)") (class "Default")
      (node (ref "U2") (pin "5") (pinfunction "NC_5") (pintype "tri_state+no_connect"))
    )
    (net (code "84") (name "unconnected-(U2-NC-Pad6)") (class "Default")
      (node (ref "U2") (pin "6") (pinfunction "NC_6") (pintype "tri_state+no_connect"))
    )
    (net (code "85") (name "unconnected-(U2-NC-Pad13)") (class "Default")
      (node (ref "U2") (pin "13") (pinfunction "NC_13") (pintype "tri_state+no_connect"))
    )
    (net (code "86") (name "unconnected-(U2-NC-Pad14)") (class "Default")
      (node (ref "U2") (pin "14") (pinfunction "NC_14") (pintype "tri_state+no_connect"))
    )
    (net (code "87") (name "unconnected-(U2-NC-Pad15)") (class "Default")
      (node (ref "U2") (pin "15") (pinfunction "NC_15") (pintype "tri_state+no_connect"))
    )
    (net (code "88") (name "unconnected-(U2-OW-Pad16)") (class "Default")
      (node (ref "U2") (pin "16") (pinfunction "OW_16") (pintype "bidirectional+no_connect"))
    )
    (net (code "89") (name "unconnected-(U4-ACK-Pad15)") (class "Default")
      (node (ref "U4") (pin "15") (pinfunction "ACK_15") (pintype "tri_state+no_connect"))
    )
    (net (code "90") (name "unconnected-(U4-NC-Pad3)") (class "Default")
      (node (ref "U4") (pin "3") (pinfunction "NC_3") (pintype "tri_state+no_connect"))
    )
    (net (code "91") (name "unconnected-(U4-NC-Pad4)") (class "Default")
      (node (ref "U4") (pin "4") (pinfunction "NC_4") (pintype "tri_state+no_connect"))
    )
    (net (code "92") (name "unconnected-(U4-NC-Pad5)") (class "Default")
      (node (ref "U4") (pin "5") (pinfunction "NC_5") (pintype "tri_state+no_connect"))
    )
    (net (code "93") (name "unconnected-(U4-NC-Pad6)") (class "Default")
      (node (ref "U4") (pin "6") (pinfunction "NC_6") (pintype "tri_state+no_connect"))
    )
    (net (code "94") (name "unconnected-(U4-NC-Pad10)") (class "Default")
      (node (ref "U4") (pin "10") (pinfunction "NC_10") (pintype "tri_state+no_connect"))
    )
    (net (code "95") (name "unconnected-(U4-NC-Pad11)") (class "Default")
      (node (ref "U4") (pin "11") (pinfunction "NC_11") (pintype "tri_state+no_connect"))
    )
    (net (code "96") (name "unconnected-(U4-NC-Pad12)") (class "Default")
      (node (ref "U4") (pin "12") (pinfunction "NC_12") (pintype "tri_state+no_connect"))
    )
    (net (code "97") (name "unconnected-(U4-RST-Pad2)") (class "Default")
      (node (ref "U4") (pin "2") (pinfunction "RST_2") (pintype "input+no_connect"))
    )
    (net (code "98") (name "unconnected-(U4-STB-Pad1)") (class "Default")
      (node (ref "U4") (pin "1") (pinfunction "STB_1") (pintype "input+no_connect"))
    )
    (net (code "99") (name "unconnected-(U4-STB-Pad16)") (class "Default")
      (node (ref "U4") (pin "16") (pinfunction "STB_16") (pintype "input+no_connect"))
    )
    (net (code "100") (name "unconnected-(U5-INT-Pad15)") (class "Default")
      (node (ref "U5") (pin "15") (pinfunction "INT_15") (pintype "tri_state+no_connect"))
    )
    (net (code "101") (name "unconnected-(U5-NC-Pad1)") (class "Default")
      (node (ref "U5") (pin "1") (pinfunction "NC_1") (pintype "tri_state+no_connect"))
    )
    (net (code "102") (name "unconnected-(U5-NC-Pad2)") (class "Default")
      (node (ref "U5") (pin "2") (pinfunction "NC_2") (pintype "input+no_connect"))
    )
    (net (code "103") (name "unconnected-(U5-NC-Pad10)") (class "Default")
      (node (ref "U5") (pin "10") (pinfunction "NC_10") (pintype "open_emitter+no_connect"))
    )
    (net (code "104") (name "unconnected-(U5-NC-Pad13)") (class "Default")
      (node (ref "U5") (pin "13") (pinfunction "NC_13") (pintype "input+no_connect"))
    )
    (net (code "105") (name "unconnected-(U5-NC-Pad14)") (class "Default")
      (node (ref "U5") (pin "14") (pinfunction "NC_14") (pintype "output+no_connect"))
    )
    (net (code "106") (name "unconnected-(U5-NC-Pad16)") (class "Default")
      (node (ref "U5") (pin "16") (pinfunction "NC_16") (pintype "tri_state+no_connect"))
    )
    (net (code "107") (name "unconnected-(U5-SCL-Pad12)") (class "Default")
      (node (ref "U5") (pin "12") (pinfunction "SCL_12") (pintype "input+no_connect"))
    )
    (net (code "108") (name "unconnected-(U5-SDA-Pad11)") (class "Default")
      (node (ref "U5") (pin "11") (pinfunction "SDA_11") (pintype "bidirectional+no_connect"))
    )
    (net (code "109") (name "unconnected-(U7A-NC-Pad5)") (class "Default")
      (node (ref "U7") (pin "5") (pinfunction "NC_5") (pintype "bidirectional+no_connect"))
    )
    (net (code "110") (name "unconnected-(U7A-NC-Pad6)") (class "Default")
      (node (ref "U7") (pin "6") (pinfunction "NC_6") (pintype "bidirectional+no_connect"))
    )
    (net (code "111") (name "unconnected-(U7A-NC-Pad26)") (class "Default")
      (node (ref "U7") (pin "26") (pinfunction "NC_26") (pintype "bidirectional+no_connect"))
    )
    (net (code "112") (name "unconnected-(U7B-NC-Pad68)") (class "Default")
      (node (ref "U7") (pin "68") (pinfunction "NC_68") (pintype "bidirectional+no_connect"))
    )
  )
)
